# Conexion_actuadores.net
KiCad netlist of a schematic drawn in Altium Designer
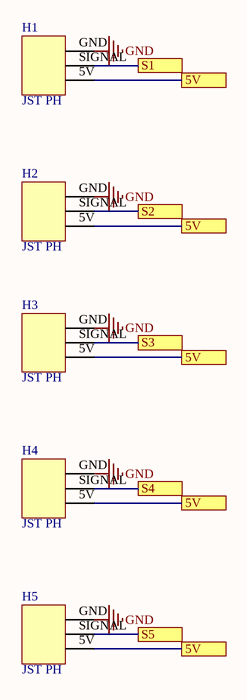
[diagram p0: Conexion_actuadores.SchDoc]

(export (version "E")
  (design (tool "Eeschema 10.0.6"))
  (components
    (comp (ref "H1")
      (value "JST PH")
      (footprint "Conector_Servo")
      (libsource (lib "Schlib-ESP-01S-WS-V1.0") (part "Header_Pin_1X3_Servo"))
    )
    (comp (ref "H2")
      (value "JST PH")
      (footprint "Conector_Servo")
      (libsource (lib "Schlib-ESP-01S-WS-V1.0") (part "Header_Pin_1X3_Servo"))
    )
    (comp (ref "H3")
      (value "JST PH")
      (footprint "Conector_Servo")
      (libsource (lib "Schlib-ESP-01S-WS-V1.0") (part "Header_Pin_1X3_Servo"))
    )
    (comp (ref "H4")
      (value "JST PH")
      (footprint "Conector_Servo")
      (libsource (lib "Schlib-ESP-01S-WS-V1.0") (part "Header_Pin_1X3_Servo"))
    )
    (comp (ref "H5")
      (value "JST PH")
      (footprint "Conector_Servo")
      (libsource (lib "Schlib-ESP-01S-WS-V1.0") (part "Header_Pin_1X3_Servo"))
    )
  )
  (nets
    (net (code "1") (name "/5V") (class "Default")
      (node (ref "H1") (pin "5V") (pinfunction "5V_5V") (pintype "passive"))
      (node (ref "H2") (pin "5V") (pinfunction "5V_5V") (pintype "passive"))
      (node (ref "H3") (pin "5V") (pinfunction "5V_5V") (pintype "passive"))
      (node (ref "H4") (pin "5V") (pinfunction "5V_5V") (pintype "passive"))
      (node (ref "H5") (pin "5V") (pinfunction "5V_5V") (pintype "passive"))
    )
    (net (code "2") (name "/S1") (class "Default")
      (node (ref "H1") (pin "SIGNAL") (pinfunction "SIGNAL_SIGNAL") (pintype "passive"))
    )
    (net (code "3") (name "/S2") (class "Default")
      (node (ref "H2") (pin "SIGNAL") (pinfunction "SIGNAL_SIGNAL") (pintype "passive"))
    )
    (net (code "4") (name "/S3") (class "Default")
      (node (ref "H3") (pin "SIGNAL") (pinfunction "SIGNAL_SIGNAL") (pintype "passive"))
    )
    (net (code "5") (name "/S4") (class "Default")
      (node (ref "H4") (pin "SIGNAL") (pinfunction "SIGNAL_SIGNAL") (pintype "passive"))
    )
    (net (code "6") (name "/S5") (class "Default")
      (node (ref "H5") (pin "SIGNAL") (pinfunction "SIGNAL_SIGNAL") (pintype "passive"))
    )
    (net (code "7") (name "GND") (class "Default")
      (node (ref "H1") (pin "GND") (pinfunction "GND_GND") (pintype "passive"))
      (node (ref "H2") (pin "GND") (pinfunction "GND_GND") (pintype "passive"))
      (node (ref "H3") (pin "GND") (pinfunction "GND_GND") (pintype "passive"))
      (node (ref "H4") (pin "GND") (pinfunction "GND_GND") (pintype "passive"))
      (node (ref "H5") (pin "GND") (pinfunction "GND_GND") (pintype "passive"))
    )
  )
)
